# Sheet1.net
KiCad netlist of a schematic drawn in Altium Designer
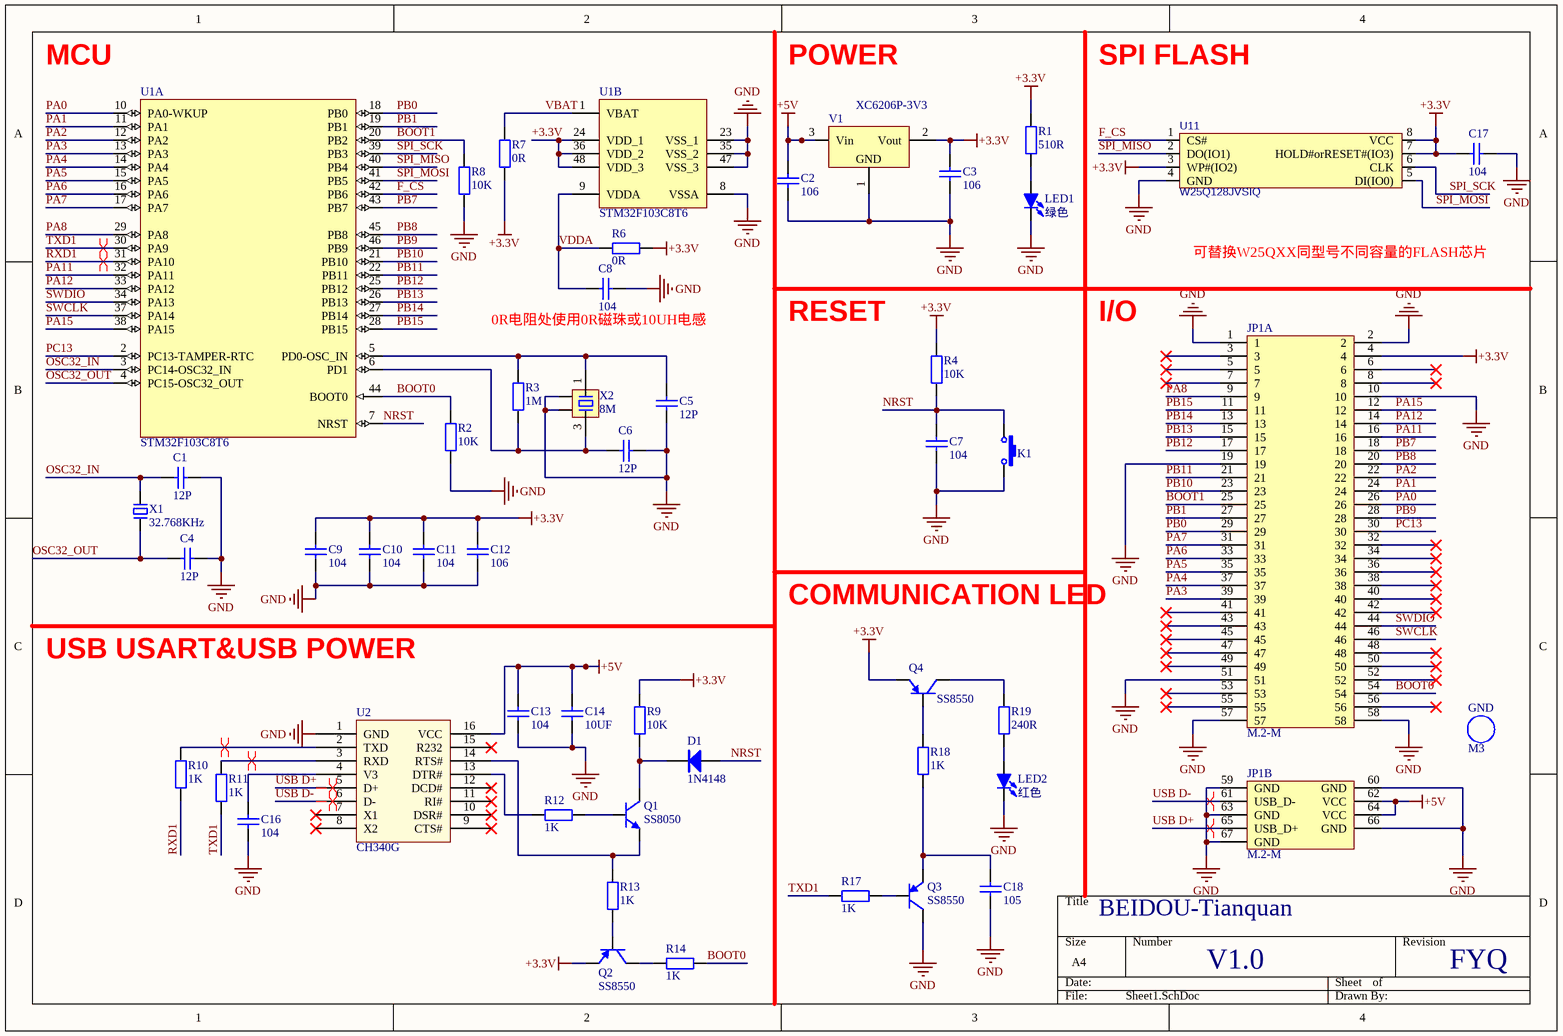
[diagram p0: Sheet1.SchDoc]

(export (version "E")
  (design (tool "Eeschema 10.0.6"))
  (components
    (comp (ref "C1")
      (value "12P")
      (footprint "C0603_L")
      (description "贴片电容")
      (libsource (lib "0.1 - 电阻-电容-电感-电位器") (part "C"))
    )
    (comp (ref "C2")
      (value "106")
      (footprint "C0603_L")
      (description "贴片电容")
      (libsource (lib "0.1 - 电阻-电容-电感-电位器") (part "C"))
    )
    (comp (ref "C3")
      (value "106")
      (footprint "C0603_L")
      (description "贴片电容")
      (libsource (lib "0.1 - 电阻-电容-电感-电位器") (part "C"))
    )
    (comp (ref "C4")
      (value "12P")
      (footprint "C0603_L")
      (description "贴片电容")
      (libsource (lib "0.1 - 电阻-电容-电感-电位器") (part "C"))
    )
    (comp (ref "C5")
      (value "12P")
      (footprint "C0603_L")
      (description "贴片电容")
      (libsource (lib "0.1 - 电阻-电容-电感-电位器") (part "C"))
    )
    (comp (ref "C6")
      (value "12P")
      (footprint "C0603_L")
      (description "贴片电容")
      (libsource (lib "0.1 - 电阻-电容-电感-电位器") (part "C"))
    )
    (comp (ref "C7")
      (value "104")
      (footprint "C0603_L")
      (description "贴片电容")
      (libsource (lib "0.1 - 电阻-电容-电感-电位器") (part "C"))
    )
    (comp (ref "C8")
      (value "104")
      (footprint "C0603_L")
      (description "贴片电容")
      (libsource (lib "0.1 - 电阻-电容-电感-电位器") (part "C"))
    )
    (comp (ref "C9")
      (value "104")
      (footprint "C0603_L")
      (description "贴片电容")
      (libsource (lib "0.1 - 电阻-电容-电感-电位器") (part "C"))
    )
    (comp (ref "C10")
      (value "104")
      (footprint "C0603_L")
      (description "贴片电容")
      (libsource (lib "0.1 - 电阻-电容-电感-电位器") (part "C"))
    )
    (comp (ref "C11")
      (value "104")
      (footprint "C0603_L")
      (description "贴片电容")
      (libsource (lib "0.1 - 电阻-电容-电感-电位器") (part "C"))
    )
    (comp (ref "C12")
      (value "106")
      (footprint "C0603_L")
      (description "贴片电容")
      (libsource (lib "0.1 - 电阻-电容-电感-电位器") (part "C"))
    )
    (comp (ref "C13")
      (value "104")
      (footprint "C0603_L")
      (description "贴片电容")
      (libsource (lib "0.1 - 电阻-电容-电感-电位器") (part "C"))
    )
    (comp (ref "C14")
      (value "10UF")
      (footprint "C0603_L")
      (description "贴片电容")
      (libsource (lib "0.1 - 电阻-电容-电感-电位器") (part "C"))
    )
    (comp (ref "C16")
      (value "104")
      (footprint "C0603_L")
      (description "贴片电容")
      (libsource (lib "0.1 - 电阻-电容-电感-电位器") (part "C"))
    )
    (comp (ref "C17")
      (value "104")
      (footprint "C0603_L")
      (description "贴片电容")
      (libsource (lib "0.1 - 电阻-电容-电感-电位器") (part "C"))
    )
    (comp (ref "C18")
      (value "105")
      (footprint "C0603_L")
      (description "贴片电容")
      (libsource (lib "0.1 - 电阻-电容-电感-电位器") (part "C"))
    )
    (comp (ref "D1")
      (value "1N4148")
      (footprint "SOD-323")
      (description "开关二极管")
      (libsource (lib "0.2 - 二极管-TVS-整流桥") (part "1N4148"))
    )
    (comp (ref "GND")
      (value "M3")
      (footprint "M3 125X200")
      (description "铜柱孔")
      (libsource (lib "0.7 - 常用按键-开关-蜂鸣器-电池-测试点") (part "M3"))
    )
    (comp (ref "JP1")
      (value "M.2-M")
      (footprint "M.2-MKEY")
      (description "M.2-M接口")
      (libsource (lib "M.2接口") (part "M.2-M接口"))
    )
    (comp (ref "K1")
      (value "3x6x5")
      (footprint "SW SMD-3*4*2.5")
      (description "微动开关")
      (libsource (lib "0.7 - 常用按键-开关-蜂鸣器-电池-测试点") (part "SW-PB"))
    )
    (comp (ref "LED1")
      (value "绿色")
      (footprint "LED0603_G")
      (description "贴片LED")
      (libsource (lib "0.3 - LED发光二极管") (part "LED-SMD"))
    )
    (comp (ref "LED2")
      (value "红色")
      (footprint "LED0603_G")
      (description "贴片LED")
      (libsource (lib "0.3 - LED发光二极管") (part "LED-SMD"))
    )
    (comp (ref "Q1")
      (value "SS8050")
      (footprint "SOT23-3L")
      (description "高频放大-NPN型")
      (libsource (lib "0.4 - 三极管-场效应管-可控硅") (part "8050-SMD"))
    )
    (comp (ref "Q2")
      (value "SS8550")
      (footprint "SOT23-3L")
      (description "高频放大-PNP型")
      (libsource (lib "0.4 - 三极管-场效应管-可控硅") (part "8550-SMD"))
    )
    (comp (ref "Q3")
      (value "SS8550")
      (footprint "SOT23-3N")
      (description "高频放大-PNP型")
      (libsource (lib "0.4 - 三极管-场效应管-可控硅") (part "8550-SMD"))
    )
    (comp (ref "Q4")
      (value "SS8550")
      (footprint "SOT23-3N")
      (description "高频放大-PNP型")
      (libsource (lib "0.4 - 三极管-场效应管-可控硅") (part "8550-SMD"))
    )
    (comp (ref "R1")
      (value "510R")
      (footprint "R0603_L")
      (description "贴片电阻")
      (libsource (lib "0.1 - 电阻-电容-电感-电位器") (part "R"))
    )
    (comp (ref "R2")
      (value "10K")
      (footprint "R0603_L")
      (description "贴片电阻")
      (libsource (lib "0.1 - 电阻-电容-电感-电位器") (part "R"))
    )
    (comp (ref "R3")
      (value "1M")
      (footprint "R0603_L")
      (description "贴片电阻")
      (libsource (lib "0.1 - 电阻-电容-电感-电位器") (part "R"))
    )
    (comp (ref "R4")
      (value "10K")
      (footprint "R0603_L")
      (description "贴片电阻")
      (libsource (lib "0.1 - 电阻-电容-电感-电位器") (part "R"))
    )
    (comp (ref "R6")
      (value "0R")
      (footprint "R0603_L")
      (description "贴片电阻")
      (libsource (lib "0.1 - 电阻-电容-电感-电位器") (part "R"))
    )
    (comp (ref "R7")
      (value "0R")
      (footprint "R0603_L")
      (description "贴片电阻")
      (libsource (lib "0.1 - 电阻-电容-电感-电位器") (part "R"))
    )
    (comp (ref "R8")
      (value "10K")
      (footprint "R0603_L")
      (description "贴片电阻")
      (libsource (lib "0.1 - 电阻-电容-电感-电位器") (part "R"))
    )
    (comp (ref "R9")
      (value "10K")
      (footprint "R0603_L")
      (description "贴片电阻")
      (libsource (lib "0.1 - 电阻-电容-电感-电位器") (part "R"))
    )
    (comp (ref "R10")
      (value "1K")
      (footprint "R0603_L")
      (description "贴片电阻")
      (libsource (lib "0.1 - 电阻-电容-电感-电位器") (part "R"))
    )
    (comp (ref "R11")
      (value "1K")
      (footprint "R0603_L")
      (description "贴片电阻")
      (libsource (lib "0.1 - 电阻-电容-电感-电位器") (part "R"))
    )
    (comp (ref "R12")
      (value "1K")
      (footprint "R0603_L")
      (description "贴片电阻")
      (libsource (lib "0.1 - 电阻-电容-电感-电位器") (part "R"))
    )
    (comp (ref "R13")
      (value "1K")
      (footprint "R0603_L")
      (description "贴片电阻")
      (libsource (lib "0.1 - 电阻-电容-电感-电位器") (part "R"))
    )
    (comp (ref "R14")
      (value "1K")
      (footprint "R0603_L")
      (description "贴片电阻")
      (libsource (lib "0.1 - 电阻-电容-电感-电位器") (part "R"))
    )
    (comp (ref "R17")
      (value "1K")
      (footprint "R0603_L")
      (description "贴片电阻")
      (libsource (lib "0.1 - 电阻-电容-电感-电位器") (part "R"))
    )
    (comp (ref "R18")
      (value "1K")
      (footprint "R0603_L")
      (description "贴片电阻")
      (libsource (lib "0.1 - 电阻-电容-电感-电位器") (part "R"))
    )
    (comp (ref "R19")
      (value "240R")
      (footprint "R0603_L")
      (description "贴片电阻")
      (libsource (lib "0.1 - 电阻-电容-电感-电位器") (part "R"))
    )
    (comp (ref "U1")
      (value "STM32F103C8T6")
      (footprint "LQFP48_N")
      (libsource (lib "2.4 - STM32 F1系列单片机") (part "STM32F103C8T6"))
    )
    (comp (ref "U2")
      (value "CH340G")
      (footprint "SOP16_N")
      (description "串口转USB芯片")
      (libsource (lib "1.9 - CH340系列编程器芯片") (part "CH340G"))
    )
    (comp (ref "U11")
      (value "W25Q128JVSIQ")
      (footprint "SOIC-8W")
      (description "SPI FLASH")
      (libsource (lib "1.2 - 存储器-传感元件") (part "W25Q128"))
    )
    (comp (ref "V1")
      (value "XC6206P-3V3")
      (footprint "SOT23-3N")
      (description "三端稳压芯片")
      (libsource (lib "1.1 - 电源类芯片") (part "XC6206P"))
    )
    (comp (ref "X1")
      (value "32.768KHz")
      (footprint "OSC 3215-2P")
      (description "2脚无源脚晶振")
      (libsource (lib "0.5 - 保险丝-晶振-光耦") (part "XTAL-2P"))
    )
    (comp (ref "X2")
      (value "8M")
      (footprint "OSC 3225-4P")
      (description "4脚无源晶振")
      (libsource (lib "0.5 - 保险丝-晶振-光耦") (part "XTAL-4P"))
    )
  )
  (nets
    (net (code "1") (name "+3.3V") (class "Default")
      (node (ref "C10") (pin "2") (pinfunction "2_2") (pintype "passive"))
      (node (ref "C11") (pin "2") (pinfunction "2_2") (pintype "passive"))
      (node (ref "C12") (pin "2") (pinfunction "2_2") (pintype "passive"))
      (node (ref "C17") (pin "2") (pinfunction "2_2") (pintype "passive"))
      (node (ref "C3") (pin "2") (pinfunction "2_2") (pintype "passive"))
      (node (ref "C9") (pin "2") (pinfunction "2_2") (pintype "passive"))
      (node (ref "JP1") (pin "4") (pinfunction "4_4") (pintype "passive"))
      (node (ref "Q2") (pin "2") (pinfunction "E_2") (pintype "passive"))
      (node (ref "Q4") (pin "2") (pinfunction "E_2") (pintype "passive"))
      (node (ref "R1") (pin "1") (pinfunction "1_1") (pintype "passive"))
      (node (ref "R4") (pin "1") (pinfunction "1_1") (pintype "passive"))
      (node (ref "R6") (pin "1") (pinfunction "1_1") (pintype "passive"))
      (node (ref "R7") (pin "1") (pinfunction "1_1") (pintype "passive"))
      (node (ref "R9") (pin "1") (pinfunction "1_1") (pintype "passive"))
      (node (ref "U1") (pin "24") (pinfunction "VDD_1_24") (pintype "power_in"))
      (node (ref "U1") (pin "36") (pinfunction "VDD_2_36") (pintype "power_in"))
      (node (ref "U1") (pin "48") (pinfunction "VDD_3_48") (pintype "power_in"))
      (node (ref "U11") (pin "3") (pinfunction "WP#(IO2)_3") (pintype "passive"))
      (node (ref "U11") (pin "7") (pinfunction "HOLD#orRESET#(IO3)_7") (pintype "passive"))
      (node (ref "U11") (pin "8") (pinfunction "VCC_8") (pintype "passive"))
      (node (ref "V1") (pin "2") (pinfunction "Vout_2") (pintype "passive"))
    )
    (net (code "2") (name "+5V") (class "Default")
      (node (ref "C13") (pin "2") (pinfunction "2_2") (pintype "passive"))
      (node (ref "C14") (pin "2") (pinfunction "2_2") (pintype "passive"))
      (node (ref "C2") (pin "2") (pinfunction "2_2") (pintype "passive"))
      (node (ref "JP1") (pin "62") (pinfunction "VCC_62") (pintype "passive"))
      (node (ref "JP1") (pin "64") (pinfunction "VCC_64") (pintype "passive"))
      (node (ref "U2") (pin "16") (pinfunction "VCC_16") (pintype "passive"))
      (node (ref "V1") (pin "3") (pinfunction "Vin_3") (pintype "passive"))
    )
    (net (code "3") (name "/BOOT0") (class "Default")
      (node (ref "JP1") (pin "54") (pinfunction "54_54") (pintype "passive"))
      (node (ref "R14") (pin "2") (pinfunction "2_2") (pintype "passive"))
      (node (ref "R2") (pin "2") (pinfunction "2_2") (pintype "passive"))
      (node (ref "U1") (pin "44") (pinfunction "BOOT0_44") (pintype "input"))
    )
    (net (code "4") (name "/BOOT1") (class "Default")
      (node (ref "JP1") (pin "25") (pinfunction "25_25") (pintype "passive"))
      (node (ref "R8") (pin "2") (pinfunction "2_2") (pintype "passive"))
      (node (ref "U1") (pin "20") (pinfunction "PB2_20") (pintype "bidirectional"))
    )
    (net (code "5") (name "/F_CS") (class "Default")
      (node (ref "U1") (pin "42") (pinfunction "PB6_42") (pintype "bidirectional"))
      (node (ref "U11") (pin "1") (pinfunction "CS#_1") (pintype "passive"))
    )
    (net (code "6") (name "/NRST") (class "Default")
      (node (ref "C7") (pin "2") (pinfunction "2_2") (pintype "passive"))
      (node (ref "D1") (pin "1") (pinfunction "A_1") (pintype "passive"))
      (node (ref "K1") (pin "1") (pinfunction "1_1") (pintype "passive"))
      (node (ref "R4") (pin "2") (pinfunction "2_2") (pintype "passive"))
      (node (ref "U1") (pin "7") (pinfunction "NRST_7") (pintype "bidirectional"))
    )
    (net (code "7") (name "/OSC32_IN") (class "Default")
      (node (ref "C1") (pin "1") (pinfunction "1_1") (pintype "passive"))
      (node (ref "U1") (pin "3") (pinfunction "PC14-OSC32_IN_3") (pintype "bidirectional"))
      (node (ref "X1") (pin "2") (pinfunction "2_2") (pintype "passive"))
    )
    (net (code "8") (name "/OSC32_OUT") (class "Default")
      (node (ref "C4") (pin "1") (pinfunction "1_1") (pintype "passive"))
      (node (ref "U1") (pin "4") (pinfunction "PC15-OSC32_OUT_4") (pintype "bidirectional"))
      (node (ref "X1") (pin "1") (pinfunction "1_1") (pintype "passive"))
    )
    (net (code "9") (name "/PA0") (class "Default")
      (node (ref "JP1") (pin "26") (pinfunction "26_26") (pintype "passive"))
      (node (ref "U1") (pin "10") (pinfunction "PA0-WKUP_10") (pintype "bidirectional"))
    )
    (net (code "10") (name "/PA1") (class "Default")
      (node (ref "JP1") (pin "24") (pinfunction "24_24") (pintype "passive"))
      (node (ref "U1") (pin "11") (pinfunction "PA1_11") (pintype "bidirectional"))
    )
    (net (code "11") (name "/PA2") (class "Default")
      (node (ref "JP1") (pin "22") (pinfunction "22_22") (pintype "passive"))
      (node (ref "U1") (pin "12") (pinfunction "PA2_12") (pintype "bidirectional"))
    )
    (net (code "12") (name "/PA3") (class "Default")
      (node (ref "JP1") (pin "39") (pinfunction "39_39") (pintype "passive"))
      (node (ref "U1") (pin "13") (pinfunction "PA3_13") (pintype "bidirectional"))
    )
    (net (code "13") (name "/PA4") (class "Default")
      (node (ref "JP1") (pin "37") (pinfunction "37_37") (pintype "passive"))
      (node (ref "U1") (pin "14") (pinfunction "PA4_14") (pintype "bidirectional"))
    )
    (net (code "14") (name "/PA5") (class "Default")
      (node (ref "JP1") (pin "35") (pinfunction "35_35") (pintype "passive"))
      (node (ref "U1") (pin "15") (pinfunction "PA5_15") (pintype "bidirectional"))
    )
    (net (code "15") (name "/PA6") (class "Default")
      (node (ref "JP1") (pin "33") (pinfunction "33_33") (pintype "passive"))
      (node (ref "U1") (pin "16") (pinfunction "PA6_16") (pintype "bidirectional"))
    )
    (net (code "16") (name "/PA7") (class "Default")
      (node (ref "JP1") (pin "31") (pinfunction "31_31") (pintype "passive"))
      (node (ref "U1") (pin "17") (pinfunction "PA7_17") (pintype "bidirectional"))
    )
    (net (code "17") (name "/PA8") (class "Default")
      (node (ref "JP1") (pin "9") (pinfunction "9_9") (pintype "passive"))
      (node (ref "U1") (pin "29") (pinfunction "PA8_29") (pintype "bidirectional"))
    )
    (net (code "18") (name "/PA11") (class "Default")
      (node (ref "JP1") (pin "16") (pinfunction "16_16") (pintype "passive"))
      (node (ref "U1") (pin "32") (pinfunction "PA11_32") (pintype "bidirectional"))
    )
    (net (code "19") (name "/PA12") (class "Default")
      (node (ref "JP1") (pin "14") (pinfunction "14_14") (pintype "passive"))
      (node (ref "U1") (pin "33") (pinfunction "PA12_33") (pintype "bidirectional"))
    )
    (net (code "20") (name "/PA15") (class "Default")
      (node (ref "JP1") (pin "12") (pinfunction "12_12") (pintype "passive"))
      (node (ref "U1") (pin "38") (pinfunction "PA15_38") (pintype "bidirectional"))
    )
    (net (code "21") (name "/PB0") (class "Default")
      (node (ref "JP1") (pin "29") (pinfunction "29_29") (pintype "passive"))
      (node (ref "U1") (pin "18") (pinfunction "PB0_18") (pintype "bidirectional"))
    )
    (net (code "22") (name "/PB1") (class "Default")
      (node (ref "JP1") (pin "27") (pinfunction "27_27") (pintype "passive"))
      (node (ref "U1") (pin "19") (pinfunction "PB1_19") (pintype "bidirectional"))
    )
    (net (code "23") (name "/PB7") (class "Default")
      (node (ref "JP1") (pin "18") (pinfunction "18_18") (pintype "passive"))
      (node (ref "U1") (pin "43") (pinfunction "PB7_43") (pintype "bidirectional"))
    )
    (net (code "24") (name "/PB8") (class "Default")
      (node (ref "JP1") (pin "20") (pinfunction "20_20") (pintype "passive"))
      (node (ref "U1") (pin "45") (pinfunction "PB8_45") (pintype "bidirectional"))
    )
    (net (code "25") (name "/PB9") (class "Default")
      (node (ref "JP1") (pin "28") (pinfunction "28_28") (pintype "passive"))
      (node (ref "U1") (pin "46") (pinfunction "PB9_46") (pintype "bidirectional"))
    )
    (net (code "26") (name "/PB10") (class "Default")
      (node (ref "JP1") (pin "23") (pinfunction "23_23") (pintype "passive"))
      (node (ref "U1") (pin "21") (pinfunction "PB10_21") (pintype "bidirectional"))
    )
    (net (code "27") (name "/PB11") (class "Default")
      (node (ref "JP1") (pin "21") (pinfunction "21_21") (pintype "passive"))
      (node (ref "U1") (pin "22") (pinfunction "PB11_22") (pintype "bidirectional"))
    )
    (net (code "28") (name "/PB12") (class "Default")
      (node (ref "JP1") (pin "17") (pinfunction "17_17") (pintype "passive"))
      (node (ref "U1") (pin "25") (pinfunction "PB12_25") (pintype "bidirectional"))
    )
    (net (code "29") (name "/PB13") (class "Default")
      (node (ref "JP1") (pin "15") (pinfunction "15_15") (pintype "passive"))
      (node (ref "U1") (pin "26") (pinfunction "PB13_26") (pintype "bidirectional"))
    )
    (net (code "30") (name "/PB14") (class "Default")
      (node (ref "JP1") (pin "13") (pinfunction "13_13") (pintype "passive"))
      (node (ref "U1") (pin "27") (pinfunction "PB14_27") (pintype "bidirectional"))
    )
    (net (code "31") (name "/PB15") (class "Default")
      (node (ref "JP1") (pin "11") (pinfunction "11_11") (pintype "passive"))
      (node (ref "U1") (pin "28") (pinfunction "PB15_28") (pintype "bidirectional"))
    )
    (net (code "32") (name "/PC13") (class "Default")
      (node (ref "JP1") (pin "30") (pinfunction "30_30") (pintype "passive"))
      (node (ref "U1") (pin "2") (pinfunction "PC13-TAMPER-RTC_2") (pintype "bidirectional"))
    )
    (net (code "33") (name "/RXD1") (class "Default")
      (node (ref "R10") (pin "2") (pinfunction "2_2") (pintype "passive"))
      (node (ref "U1") (pin "31") (pinfunction "PA10_31") (pintype "bidirectional"))
    )
    (net (code "34") (name "/SPI_MISO") (class "Default")
      (node (ref "U1") (pin "40") (pinfunction "PB4_40") (pintype "bidirectional"))
      (node (ref "U11") (pin "2") (pinfunction "DO(IO1)_2") (pintype "passive"))
    )
    (net (code "35") (name "/SPI_MOSI") (class "Default")
      (node (ref "U1") (pin "41") (pinfunction "PB5_41") (pintype "bidirectional"))
      (node (ref "U11") (pin "5") (pinfunction "DI(IO0)_5") (pintype "passive"))
    )
    (net (code "36") (name "/SPI_SCK") (class "Default")
      (node (ref "U1") (pin "39") (pinfunction "PB3_39") (pintype "bidirectional"))
      (node (ref "U11") (pin "6") (pinfunction "CLK_6") (pintype "passive"))
    )
    (net (code "37") (name "/SWCLK") (class "Default")
      (node (ref "JP1") (pin "46") (pinfunction "46_46") (pintype "passive"))
      (node (ref "U1") (pin "37") (pinfunction "PA14_37") (pintype "bidirectional"))
    )
    (net (code "38") (name "/SWDIO") (class "Default")
      (node (ref "JP1") (pin "44") (pinfunction "44_44") (pintype "passive"))
      (node (ref "U1") (pin "34") (pinfunction "PA13_34") (pintype "bidirectional"))
    )
    (net (code "39") (name "/TXD1") (class "Default")
      (node (ref "R11") (pin "2") (pinfunction "2_2") (pintype "passive"))
      (node (ref "R17") (pin "1") (pinfunction "1_1") (pintype "passive"))
      (node (ref "U1") (pin "30") (pinfunction "PA9_30") (pintype "bidirectional"))
    )
    (net (code "40") (name "/USB D+") (class "Default")
      (node (ref "JP1") (pin "65") (pinfunction "USB_D-_65") (pintype "passive"))
      (node (ref "U2") (pin "5") (pinfunction "D+_5") (pintype "passive"))
    )
    (net (code "41") (name "/USB D-") (class "Default")
      (node (ref "JP1") (pin "61") (pinfunction "USB_D+_61") (pintype "passive"))
      (node (ref "U2") (pin "6") (pinfunction "D-_6") (pintype "passive"))
    )
    (net (code "42") (name "/VBAT") (class "Default")
      (node (ref "R7") (pin "2") (pinfunction "2_2") (pintype "passive"))
      (node (ref "U1") (pin "1") (pinfunction "VBAT_1") (pintype "power_in"))
    )
    (net (code "43") (name "/VDDA") (class "Default")
      (node (ref "C8") (pin "1") (pinfunction "1_1") (pintype "passive"))
      (node (ref "R6") (pin "2") (pinfunction "2_2") (pintype "passive"))
      (node (ref "U1") (pin "9") (pinfunction "VDDA_9") (pintype "power_in"))
    )
    (net (code "44") (name "GND") (class "Default")
      (node (ref "C1") (pin "2") (pinfunction "2_2") (pintype "passive"))
      (node (ref "C10") (pin "1") (pinfunction "1_1") (pintype "passive"))
      (node (ref "C11") (pin "1") (pinfunction "1_1") (pintype "passive"))
      (node (ref "C12") (pin "1") (pinfunction "1_1") (pintype "passive"))
      (node (ref "C13") (pin "1") (pinfunction "1_1") (pintype "passive"))
      (node (ref "C14") (pin "1") (pinfunction "1_1") (pintype "passive"))
      (node (ref "C16") (pin "1") (pinfunction "1_1") (pintype "passive"))
      (node (ref "C17") (pin "1") (pinfunction "1_1") (pintype "passive"))
      (node (ref "C18") (pin "1") (pinfunction "1_1") (pintype "passive"))
      (node (ref "C2") (pin "1") (pinfunction "1_1") (pintype "passive"))
      (node (ref "C3") (pin "1") (pinfunction "1_1") (pintype "passive"))
      (node (ref "C4") (pin "2") (pinfunction "2_2") (pintype "passive"))
      (node (ref "C5") (pin "1") (pinfunction "1_1") (pintype "passive"))
      (node (ref "C6") (pin "2") (pinfunction "2_2") (pintype "passive"))
      (node (ref "C7") (pin "1") (pinfunction "1_1") (pintype "passive"))
      (node (ref "C8") (pin "2") (pinfunction "2_2") (pintype "passive"))
      (node (ref "C9") (pin "1") (pinfunction "1_1") (pintype "passive"))
      (node (ref "JP1") (pin "1") (pinfunction "1_1") (pintype "passive"))
      (node (ref "JP1") (pin "10") (pinfunction "10_10") (pintype "passive"))
      (node (ref "JP1") (pin "19") (pinfunction "19_19") (pintype "passive"))
      (node (ref "JP1") (pin "2") (pinfunction "2_2") (pintype "passive"))
      (node (ref "JP1") (pin "51") (pinfunction "51_51") (pintype "passive"))
      (node (ref "JP1") (pin "57") (pinfunction "57_57") (pintype "passive"))
      (node (ref "JP1") (pin "58") (pinfunction "58_58") (pintype "passive"))
      (node (ref "JP1") (pin "59") (pinfunction "GND_59") (pintype "passive"))
      (node (ref "JP1") (pin "60") (pinfunction "GND_60") (pintype "passive"))
      (node (ref "JP1") (pin "63") (pinfunction "GND_63") (pintype "passive"))
      (node (ref "JP1") (pin "66") (pinfunction "GND_66") (pintype "passive"))
      (node (ref "JP1") (pin "67") (pinfunction "GND_67") (pintype "passive"))
      (node (ref "K1") (pin "2") (pinfunction "2_2") (pintype "passive"))
      (node (ref "LED1") (pin "2") (pinfunction "K_2") (pintype "passive"))
      (node (ref "LED2") (pin "2") (pinfunction "K_2") (pintype "passive"))
      (node (ref "Q3") (pin "3") (pinfunction "C_3") (pintype "passive"))
      (node (ref "R2") (pin "1") (pinfunction "1_1") (pintype "passive"))
      (node (ref "R8") (pin "1") (pinfunction "1_1") (pintype "passive"))
      (node (ref "U1") (pin "23") (pinfunction "VSS_1_23") (pintype "power_in"))
      (node (ref "U1") (pin "35") (pinfunction "VSS_2_35") (pintype "power_in"))
      (node (ref "U1") (pin "47") (pinfunction "VSS_3_47") (pintype "power_in"))
      (node (ref "U1") (pin "8") (pinfunction "VSSA_8") (pintype "power_in"))
      (node (ref "U11") (pin "4") (pinfunction "GND_4") (pintype "passive"))
      (node (ref "U2") (pin "1") (pinfunction "GND_1") (pintype "passive"))
      (node (ref "V1") (pin "1") (pinfunction "GND_1") (pintype "passive"))
      (node (ref "X2") (pin "2") (pinfunction "2_2") (pintype "passive"))
      (node (ref "X2") (pin "4") (pinfunction "4_4") (pintype "passive"))
    )
    (net (code "45") (name "Net-(D1-K)") (class "Default")
      (node (ref "D1") (pin "2") (pinfunction "K_2") (pintype "passive"))
      (node (ref "Q1") (pin "3") (pinfunction "C_3") (pintype "passive"))
      (node (ref "R9") (pin "2") (pinfunction "2_2") (pintype "passive"))
    )
    (net (code "46") (name "Net-(LED1-A)") (class "Default")
      (node (ref "LED1") (pin "1") (pinfunction "A_1") (pintype "passive"))
      (node (ref "R1") (pin "2") (pinfunction "2_2") (pintype "passive"))
    )
    (net (code "47") (name "Net-(LED2-A)") (class "Default")
      (node (ref "LED2") (pin "1") (pinfunction "A_1") (pintype "passive"))
      (node (ref "R19") (pin "1") (pinfunction "1_1") (pintype "passive"))
    )
    (net (code "48") (name "Net-(Q1-B)") (class "Default")
      (node (ref "Q1") (pin "1") (pinfunction "B_1") (pintype "passive"))
      (node (ref "R12") (pin "2") (pinfunction "2_2") (pintype "passive"))
    )
    (net (code "49") (name "Net-(Q1-E)") (class "Default")
      (node (ref "Q1") (pin "2") (pinfunction "E_2") (pintype "passive"))
      (node (ref "R13") (pin "1") (pinfunction "1_1") (pintype "passive"))
      (node (ref "U2") (pin "14") (pinfunction "RTS#_14") (pintype "passive"))
    )
    (net (code "50") (name "Net-(Q2-B)") (class "Default")
      (node (ref "Q2") (pin "1") (pinfunction "B_1") (pintype "passive"))
      (node (ref "R13") (pin "2") (pinfunction "2_2") (pintype "passive"))
    )
    (net (code "51") (name "Net-(Q2-C)") (class "Default")
      (node (ref "Q2") (pin "3") (pinfunction "C_3") (pintype "passive"))
      (node (ref "R14") (pin "1") (pinfunction "1_1") (pintype "passive"))
    )
    (net (code "52") (name "Net-(Q3-B)") (class "Default")
      (node (ref "Q3") (pin "1") (pinfunction "B_1") (pintype "passive"))
      (node (ref "R17") (pin "2") (pinfunction "2_2") (pintype "passive"))
    )
    (net (code "53") (name "Net-(Q3-E)") (class "Default")
      (node (ref "C18") (pin "2") (pinfunction "2_2") (pintype "passive"))
      (node (ref "Q3") (pin "2") (pinfunction "E_2") (pintype "passive"))
      (node (ref "R18") (pin "1") (pinfunction "1_1") (pintype "passive"))
    )
    (net (code "54") (name "Net-(Q4-B)") (class "Default")
      (node (ref "Q4") (pin "1") (pinfunction "B_1") (pintype "passive"))
      (node (ref "R18") (pin "2") (pinfunction "2_2") (pintype "passive"))
    )
    (net (code "55") (name "Net-(Q4-C)") (class "Default")
      (node (ref "Q4") (pin "3") (pinfunction "C_3") (pintype "passive"))
      (node (ref "R19") (pin "2") (pinfunction "2_2") (pintype "passive"))
    )
    (net (code "56") (name "Net-(U1A-PD0-OSC_IN)") (class "Default")
      (node (ref "C5") (pin "2") (pinfunction "2_2") (pintype "passive"))
      (node (ref "R3") (pin "1") (pinfunction "1_1") (pintype "passive"))
      (node (ref "U1") (pin "5") (pinfunction "PD0-OSC_IN_5") (pintype "bidirectional"))
      (node (ref "X2") (pin "1") (pinfunction "1_1") (pintype "passive"))
    )
    (net (code "57") (name "Net-(U1A-PD1)") (class "Default")
      (node (ref "C6") (pin "1") (pinfunction "1_1") (pintype "passive"))
      (node (ref "R3") (pin "2") (pinfunction "2_2") (pintype "passive"))
      (node (ref "U1") (pin "6") (pinfunction "PD1_6") (pintype "bidirectional"))
      (node (ref "X2") (pin "3") (pinfunction "3_3") (pintype "passive"))
    )
    (net (code "58") (name "Net-(U2-DTR#)") (class "Default")
      (node (ref "R12") (pin "1") (pinfunction "1_1") (pintype "passive"))
      (node (ref "U2") (pin "13") (pinfunction "DTR#_13") (pintype "passive"))
    )
    (net (code "59") (name "Net-(U2-RXD)") (class "Default")
      (node (ref "R11") (pin "1") (pinfunction "1_1") (pintype "passive"))
      (node (ref "U2") (pin "3") (pinfunction "RXD_3") (pintype "passive"))
    )
    (net (code "60") (name "Net-(U2-TXD)") (class "Default")
      (node (ref "R10") (pin "1") (pinfunction "1_1") (pintype "passive"))
      (node (ref "U2") (pin "2") (pinfunction "TXD_2") (pintype "passive"))
    )
    (net (code "61") (name "Net-(U2-V3)") (class "Default")
      (node (ref "C16") (pin "2") (pinfunction "2_2") (pintype "passive"))
      (node (ref "U2") (pin "4") (pinfunction "V3_4") (pintype "passive"))
    )
    (net (code "62") (name "unconnected-(JP1-Pad3)") (class "Default")
      (node (ref "JP1") (pin "3") (pinfunction "3_3") (pintype "passive+no_connect"))
    )
    (net (code "63") (name "unconnected-(JP1-Pad5)") (class "Default")
      (node (ref "JP1") (pin "5") (pinfunction "5_5") (pintype "passive+no_connect"))
    )
    (net (code "64") (name "unconnected-(JP1-Pad6)") (class "Default")
      (node (ref "JP1") (pin "6") (pinfunction "6_6") (pintype "passive+no_connect"))
    )
    (net (code "65") (name "unconnected-(JP1-Pad7)") (class "Default")
      (node (ref "JP1") (pin "7") (pinfunction "7_7") (pintype "passive+no_connect"))
    )
    (net (code "66") (name "unconnected-(JP1-Pad8)") (class "Default")
      (node (ref "JP1") (pin "8") (pinfunction "8_8") (pintype "passive+no_connect"))
    )
    (net (code "67") (name "unconnected-(JP1-Pad32)") (class "Default")
      (node (ref "JP1") (pin "32") (pinfunction "32_32") (pintype "passive+no_connect"))
    )
    (net (code "68") (name "unconnected-(JP1-Pad34)") (class "Default")
      (node (ref "JP1") (pin "34") (pinfunction "34_34") (pintype "passive+no_connect"))
    )
    (net (code "69") (name "unconnected-(JP1-Pad36)") (class "Default")
      (node (ref "JP1") (pin "36") (pinfunction "36_36") (pintype "passive+no_connect"))
    )
    (net (code "70") (name "unconnected-(JP1-Pad38)") (class "Default")
      (node (ref "JP1") (pin "38") (pinfunction "38_38") (pintype "passive+no_connect"))
    )
    (net (code "71") (name "unconnected-(JP1-Pad40)") (class "Default")
      (node (ref "JP1") (pin "40") (pinfunction "40_40") (pintype "passive+no_connect"))
    )
    (net (code "72") (name "unconnected-(JP1-Pad41)") (class "Default")
      (node (ref "JP1") (pin "41") (pinfunction "41_41") (pintype "passive+no_connect"))
    )
    (net (code "73") (name "unconnected-(JP1-Pad42)") (class "Default")
      (node (ref "JP1") (pin "42") (pinfunction "42_42") (pintype "passive+no_connect"))
    )
    (net (code "74") (name "unconnected-(JP1-Pad43)") (class "Default")
      (node (ref "JP1") (pin "43") (pinfunction "43_43") (pintype "passive+no_connect"))
    )
    (net (code "75") (name "unconnected-(JP1-Pad45)") (class "Default")
      (node (ref "JP1") (pin "45") (pinfunction "45_45") (pintype "passive+no_connect"))
    )
    (net (code "76") (name "unconnected-(JP1-Pad47)") (class "Default")
      (node (ref "JP1") (pin "47") (pinfunction "47_47") (pintype "passive+no_connect"))
    )
    (net (code "77") (name "unconnected-(JP1-Pad48)") (class "Default")
      (node (ref "JP1") (pin "48") (pinfunction "48_48") (pintype "passive+no_connect"))
    )
    (net (code "78") (name "unconnected-(JP1-Pad49)") (class "Default")
      (node (ref "JP1") (pin "49") (pinfunction "49_49") (pintype "passive+no_connect"))
    )
    (net (code "79") (name "unconnected-(JP1-Pad50)") (class "Default")
      (node (ref "JP1") (pin "50") (pinfunction "50_50") (pintype "passive+no_connect"))
    )
    (net (code "80") (name "unconnected-(JP1-Pad52)") (class "Default")
      (node (ref "JP1") (pin "52") (pinfunction "52_52") (pintype "passive+no_connect"))
    )
    (net (code "81") (name "unconnected-(JP1-Pad53)") (class "Default")
      (node (ref "JP1") (pin "53") (pinfunction "53_53") (pintype "passive+no_connect"))
    )
    (net (code "82") (name "unconnected-(JP1-Pad55)") (class "Default")
      (node (ref "JP1") (pin "55") (pinfunction "55_55") (pintype "passive+no_connect"))
    )
    (net (code "83") (name "unconnected-(JP1-Pad56)") (class "Default")
      (node (ref "JP1") (pin "56") (pinfunction "56_56") (pintype "passive+no_connect"))
    )
    (net (code "84") (name "unconnected-(U2-CTS#-Pad9)") (class "Default")
      (node (ref "U2") (pin "9") (pinfunction "CTS#_9") (pintype "passive+no_connect"))
    )
    (net (code "85") (name "unconnected-(U2-DCD#-Pad12)") (class "Default")
      (node (ref "U2") (pin "12") (pinfunction "DCD#_12") (pintype "passive+no_connect"))
    )
    (net (code "86") (name "unconnected-(U2-DSR#-Pad10)") (class "Default")
      (node (ref "U2") (pin "10") (pinfunction "DSR#_10") (pintype "passive+no_connect"))
    )
    (net (code "87") (name "unconnected-(U2-R232-Pad15)") (class "Default")
      (node (ref "U2") (pin "15") (pinfunction "R232_15") (pintype "passive+no_connect"))
    )
    (net (code "88") (name "unconnected-(U2-RI#-Pad11)") (class "Default")
      (node (ref "U2") (pin "11") (pinfunction "RI#_11") (pintype "passive+no_connect"))
    )
    (net (code "89") (name "unconnected-(U2-X1-Pad7)") (class "Default")
      (node (ref "U2") (pin "7") (pinfunction "X1_7") (pintype "passive+no_connect"))
    )
    (net (code "90") (name "unconnected-(U2-X2-Pad8)") (class "Default")
      (node (ref "U2") (pin "8") (pinfunction "X2_8") (pintype "passive+no_connect"))
    )
  )
)
